# sx-HX711_V_1_0.net
KiCad netlist of a schematic drawn in EAGLE
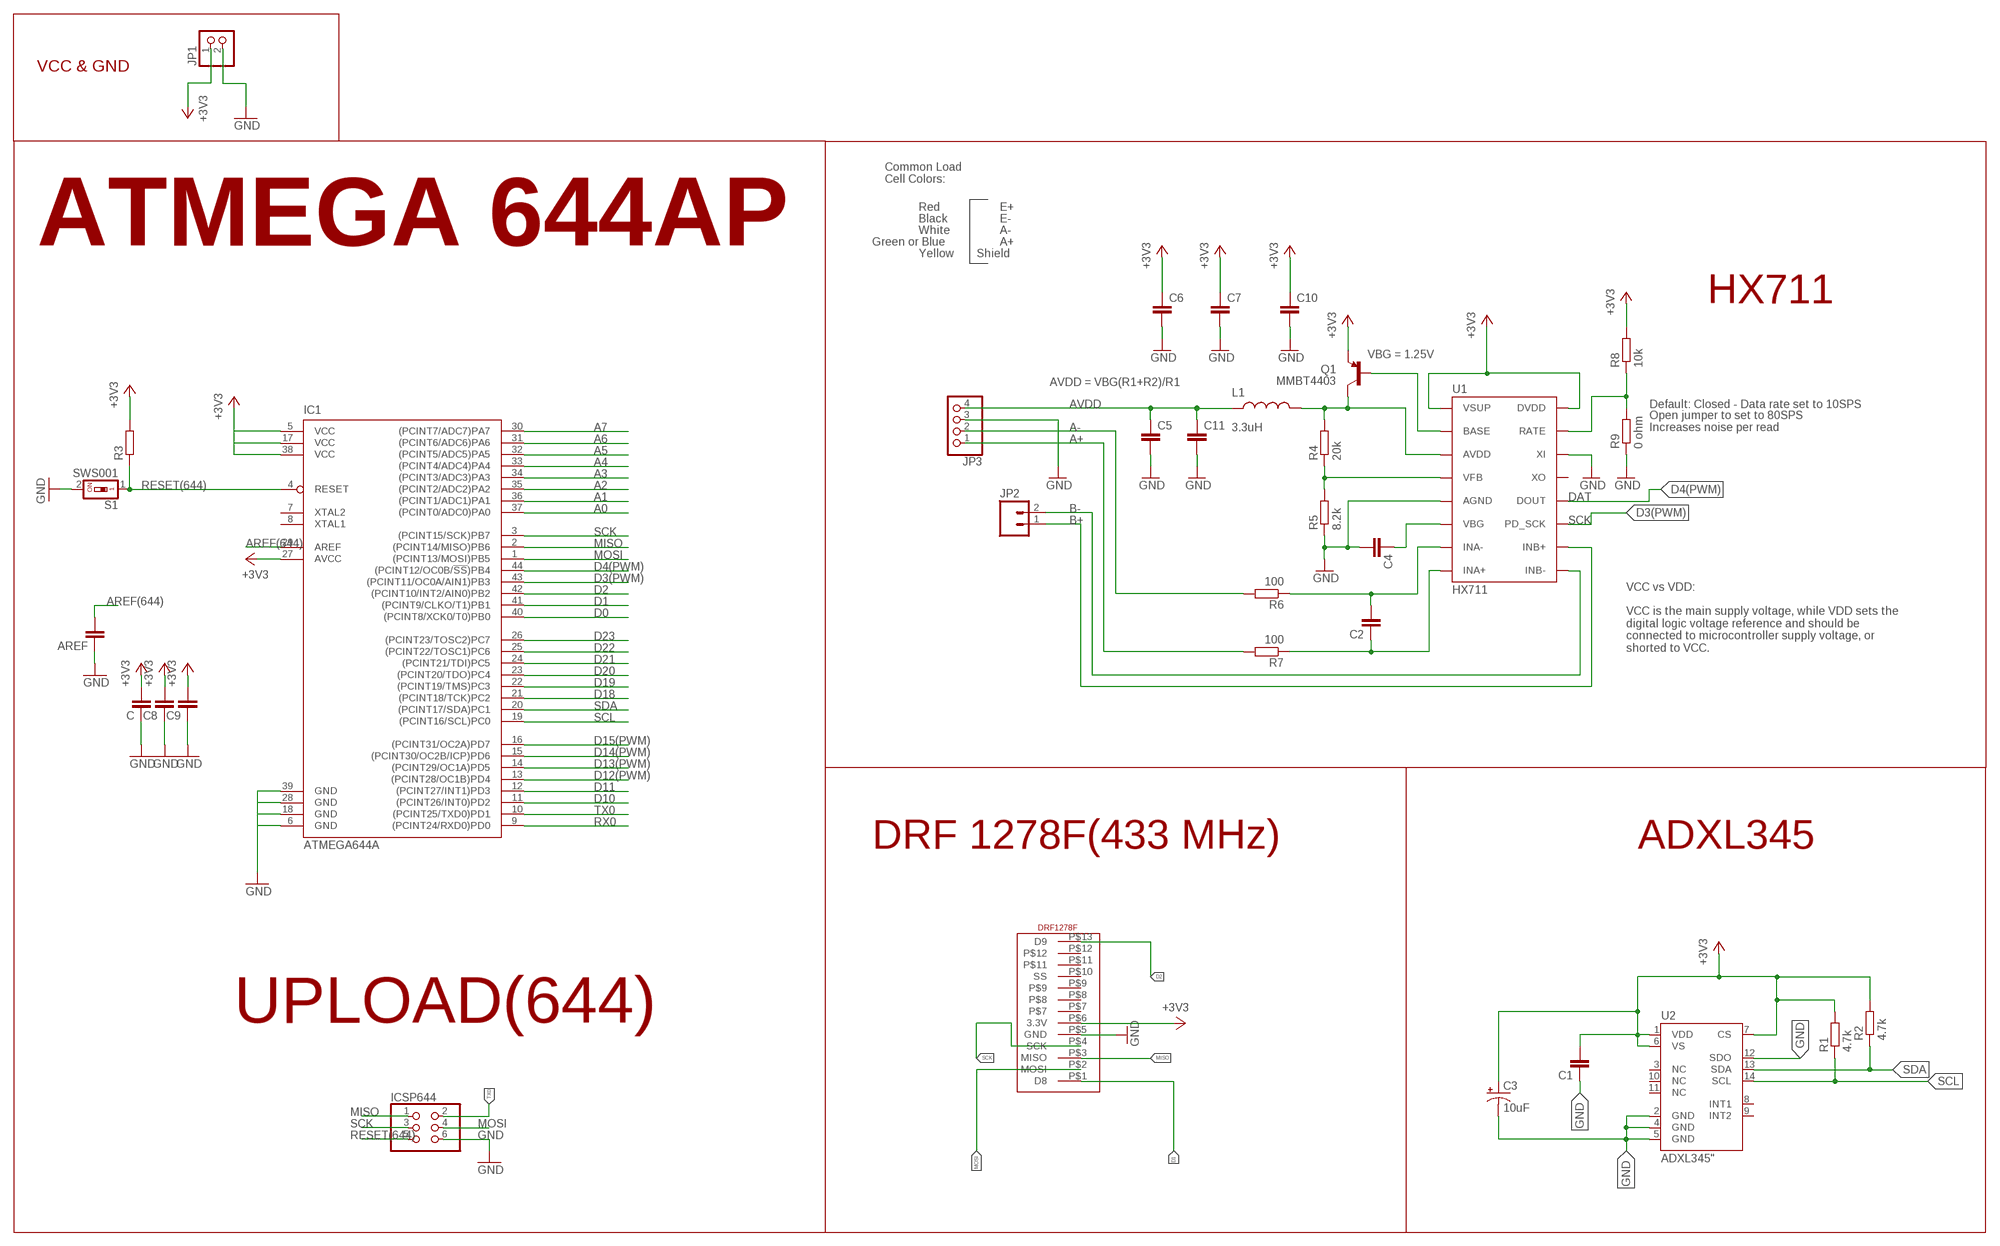
[diagram p0: schematic, sheet 1]

(export (version "E")
  (design (tool "Eeschema 10.0.6"))
  (components
    (comp (ref "AREF")
      (value "100nF")
      (footprint "eagle-import:C0805")
      (libsource (lib "eagle-import") (part "C-EUC0805"))
    )
    (comp (ref "C")
      (value "22 uF")
      (footprint "eagle-import:C0805")
      (libsource (lib "eagle-import") (part "C-EUC0805"))
    )
    (comp (ref "C1")
      (value "0.1uF")
      (footprint "eagle-import:C0805")
      (libsource (lib "eagle-import") (part "C-EUC0805"))
    )
    (comp (ref "C2")
      (value "0.1uF")
      (footprint "eagle-import:C0805")
      (libsource (lib "eagle-import") (part "C-EUC0805"))
    )
    (comp (ref "C3")
      (value "10uF")
      (footprint "eagle-import:EIA3216")
      (libsource (lib "eagle-import") (part "CAP_POL1206"))
    )
    (comp (ref "C4")
      (value "0.1uF")
      (footprint "eagle-import:C0805")
      (libsource (lib "eagle-import") (part "C-EUC0805"))
    )
    (comp (ref "C5")
      (value "0.1uF")
      (footprint "eagle-import:C0805")
      (libsource (lib "eagle-import") (part "C-EUC0805"))
    )
    (comp (ref "C6")
      (value "0.1uF")
      (footprint "eagle-import:C0805")
      (libsource (lib "eagle-import") (part "C-EUC0805"))
    )
    (comp (ref "C7")
      (value "0.1uF")
      (footprint "eagle-import:C0805")
      (libsource (lib "eagle-import") (part "C-EUC0805"))
    )
    (comp (ref "C8")
      (value "100nF")
      (footprint "eagle-import:C0805")
      (libsource (lib "eagle-import") (part "C-EUC0805"))
    )
    (comp (ref "C9")
      (value "100nF")
      (footprint "eagle-import:C0805")
      (libsource (lib "eagle-import") (part "C-EUC0805"))
    )
    (comp (ref "C10")
      (value "10uF")
      (footprint "eagle-import:C0805")
      (libsource (lib "eagle-import") (part "C-EUC0805"))
    )
    (comp (ref "C11")
      (value "10uF")
      (footprint "eagle-import:C0805")
      (libsource (lib "eagle-import") (part "C-EUC0805"))
    )
    (comp (ref "IC1")
      (value "ATMEGA644A")
      (footprint "eagle-import:TQFP44")
      (fields (field (name "MPN") "ATMEGA644PV-10AU"))
      (libsource (lib "eagle-import") (part "ATMEGA644A"))
    )
    (comp (ref "ICSP644")
      (value "PINHD-2X3")
      (footprint "eagle-import:2X03")
      (libsource (lib "eagle-import") (part "PINHD-2X3"))
    )
    (comp (ref "JP1")
      (value "PINHD-1X2")
      (footprint "eagle-import:1X02")
      (libsource (lib "eagle-import") (part "PINHD-1X2"))
    )
    (comp (ref "JP2")
      (value "M02PTH")
      (footprint "eagle-import:1X02")
      (libsource (lib "eagle-import") (part "M02PTH"))
    )
    (comp (ref "JP3")
      (value "PINHD-1X4")
      (footprint "eagle-import:1X04")
      (libsource (lib "eagle-import") (part "PINHD-1X4"))
    )
    (comp (ref "L1")
      (value "3.3uH")
      (footprint "eagle-import:0805")
      (libsource (lib "eagle-import") (part "INDUCTOR0805-IND"))
    )
    (comp (ref "Q1")
      (value "MMBT4403")
      (footprint "eagle-import:SOT23-3")
      (libsource (lib "eagle-import") (part "TRANSISTOR_PNPMMBT4403"))
    )
    (comp (ref "R1")
      (value "4.7k")
      (footprint "eagle-import:R0805")
      (libsource (lib "eagle-import") (part "R-EU_R0805"))
    )
    (comp (ref "R2")
      (value "4.7k")
      (footprint "eagle-import:R0805")
      (libsource (lib "eagle-import") (part "R-EU_R0805"))
    )
    (comp (ref "R3")
      (value "R-EU_R0805")
      (footprint "eagle-import:R0805")
      (libsource (lib "eagle-import") (part "R-EU_R0805"))
    )
    (comp (ref "R4")
      (value "20k")
      (footprint "eagle-import:R0805")
      (libsource (lib "eagle-import") (part "R-EU_R0805"))
    )
    (comp (ref "R5")
      (value "8.2k")
      (footprint "eagle-import:R0805")
      (libsource (lib "eagle-import") (part "R-EU_R0805"))
    )
    (comp (ref "R6")
      (value "100")
      (footprint "eagle-import:R0805")
      (libsource (lib "eagle-import") (part "R-EU_R0805"))
    )
    (comp (ref "R7")
      (value "100")
      (footprint "eagle-import:R0805")
      (libsource (lib "eagle-import") (part "R-EU_R0805"))
    )
    (comp (ref "R8")
      (value "10k")
      (footprint "eagle-import:R0805")
      (libsource (lib "eagle-import") (part "R-EU_R0805"))
    )
    (comp (ref "R9")
      (value "0 ohm")
      (footprint "eagle-import:R0805")
      (libsource (lib "eagle-import") (part "R-EU_R0805"))
    )
    (comp (ref "S1")
      (value "SWS001")
      (footprint "eagle-import:SMS-001")
      (libsource (lib "eagle-import") (part "SWS001"))
    )
    (comp (ref "U$1")
      (value "DRF1278F")
      (footprint "eagle-import:DIP13")
      (libsource (lib "eagle-import") (part "DRF1278F"))
    )
    (comp (ref "U1")
      (value "HX711")
      (footprint "eagle-import:SO16")
      (libsource (lib "eagle-import") (part "HX711HX711"))
    )
    (comp (ref "U2")
      (value "ADXL345\"")
      (footprint "eagle-import:ADXL3451_1")
      (libsource (lib "eagle-import") (part "ADXL345{dblquote}"))
    )
  )
  (nets
    (net (code "1") (name "+3V3") (class "Default")
      (node (ref "C") (pin "2") (pinfunction "2_2") (pintype "passive"))
      (node (ref "C1") (pin "2") (pinfunction "2_2") (pintype "passive"))
      (node (ref "C10") (pin "1") (pinfunction "1_1") (pintype "passive"))
      (node (ref "C3") (pin "A") (pinfunction "+_A") (pintype "passive"))
      (node (ref "C6") (pin "1") (pinfunction "1_1") (pintype "passive"))
      (node (ref "C7") (pin "1") (pinfunction "1_1") (pintype "passive"))
      (node (ref "C8") (pin "2") (pinfunction "2_2") (pintype "passive"))
      (node (ref "C9") (pin "2") (pinfunction "2_2") (pintype "passive"))
      (node (ref "IC1") (pin "17") (pinfunction "VCC_17") (pintype "power_in"))
      (node (ref "IC1") (pin "27") (pinfunction "AVCC_27") (pintype "power_in"))
      (node (ref "IC1") (pin "38") (pinfunction "VCC_38") (pintype "power_in"))
      (node (ref "IC1") (pin "5") (pinfunction "VCC_5") (pintype "power_in"))
      (node (ref "JP1") (pin "1") (pinfunction "1_1") (pintype "passive"))
      (node (ref "Q1") (pin "2") (pinfunction "E_2") (pintype "passive"))
      (node (ref "R1") (pin "2") (pinfunction "2_2") (pintype "passive"))
      (node (ref "R2") (pin "2") (pinfunction "2_2") (pintype "passive"))
      (node (ref "R3") (pin "2") (pinfunction "2_2") (pintype "passive"))
      (node (ref "R8") (pin "2") (pinfunction "2_2") (pintype "passive"))
      (node (ref "U$1") (pin "P$6") (pinfunction "3.3V_P$6") (pintype "bidirectional"))
      (node (ref "U1") (pin "1") (pinfunction "VSUP_1") (pintype "bidirectional"))
      (node (ref "U1") (pin "16") (pinfunction "DVDD_16") (pintype "bidirectional"))
      (node (ref "U2") (pin "1") (pinfunction "VDD_1") (pintype "bidirectional"))
      (node (ref "U2") (pin "6") (pinfunction "VS_6") (pintype "bidirectional"))
      (node (ref "U2") (pin "7") (pinfunction "CS_7") (pintype "bidirectional"))
    )
    (net (code "2") (name "/A+") (class "Default")
      (node (ref "JP3") (pin "1") (pinfunction "1_1") (pintype "passive"))
      (node (ref "R7") (pin "2") (pinfunction "2_2") (pintype "passive"))
    )
    (net (code "3") (name "/A-") (class "Default")
      (node (ref "JP3") (pin "2") (pinfunction "2_2") (pintype "passive"))
      (node (ref "R6") (pin "2") (pinfunction "2_2") (pintype "passive"))
    )
    (net (code "4") (name "/A0") (class "Default")
      (node (ref "IC1") (pin "37") (pinfunction "(PCINT0/ADC0)PA0_37") (pintype "bidirectional"))
    )
    (net (code "5") (name "/A1") (class "Default")
      (node (ref "IC1") (pin "36") (pinfunction "(PCINT1/ADC1)PA1_36") (pintype "bidirectional"))
    )
    (net (code "6") (name "/A2") (class "Default")
      (node (ref "IC1") (pin "35") (pinfunction "(PCINT2/ADC2)PA2_35") (pintype "bidirectional"))
    )
    (net (code "7") (name "/A3") (class "Default")
      (node (ref "IC1") (pin "34") (pinfunction "(PCINT3/ADC3)PA3_34") (pintype "bidirectional"))
    )
    (net (code "8") (name "/A4") (class "Default")
      (node (ref "IC1") (pin "33") (pinfunction "(PCINT4/ADC4)PA4_33") (pintype "bidirectional"))
    )
    (net (code "9") (name "/A5") (class "Default")
      (node (ref "IC1") (pin "32") (pinfunction "(PCINT5/ADC5)PA5_32") (pintype "bidirectional"))
    )
    (net (code "10") (name "/A6") (class "Default")
      (node (ref "IC1") (pin "31") (pinfunction "(PCINT6/ADC6)PA6_31") (pintype "bidirectional"))
    )
    (net (code "11") (name "/A7") (class "Default")
      (node (ref "IC1") (pin "30") (pinfunction "(PCINT7/ADC7)PA7_30") (pintype "bidirectional"))
    )
    (net (code "12") (name "/AREF(644)") (class "Default")
      (node (ref "AREF") (pin "2") (pinfunction "2_2") (pintype "passive"))
      (node (ref "IC1") (pin "29") (pinfunction "AREF_29") (pintype "passive"))
    )
    (net (code "13") (name "/AVDD") (class "Default")
      (node (ref "C11") (pin "1") (pinfunction "1_1") (pintype "passive"))
      (node (ref "C5") (pin "1") (pinfunction "1_1") (pintype "passive"))
      (node (ref "JP3") (pin "4") (pinfunction "4_4") (pintype "passive"))
      (node (ref "L1") (pin "1") (pinfunction "1_1") (pintype "passive"))
    )
    (net (code "14") (name "/B+") (class "Default")
      (node (ref "JP2") (pin "1") (pinfunction "1_1") (pintype "passive"))
      (node (ref "U1") (pin "10") (pinfunction "INB+_10") (pintype "bidirectional"))
    )
    (net (code "15") (name "/B-") (class "Default")
      (node (ref "JP2") (pin "2") (pinfunction "2_2") (pintype "passive"))
      (node (ref "U1") (pin "9") (pinfunction "INB-_9") (pintype "bidirectional"))
    )
    (net (code "16") (name "/D0") (class "Default")
      (node (ref "IC1") (pin "40") (pinfunction "(PCINT8/XCK0/T0)PB0_40") (pintype "bidirectional"))
    )
    (net (code "17") (name "/D10") (class "Default")
      (node (ref "IC1") (pin "11") (pinfunction "(PCINT26/INT0)PD2_11") (pintype "bidirectional"))
    )
    (net (code "18") (name "/D11") (class "Default")
      (node (ref "IC1") (pin "12") (pinfunction "(PCINT27/INT1)PD3_12") (pintype "bidirectional"))
    )
    (net (code "19") (name "/D12(PWM)") (class "Default")
      (node (ref "IC1") (pin "13") (pinfunction "(PCINT28/OC1B)PD4_13") (pintype "bidirectional"))
    )
    (net (code "20") (name "/D13(PWM)") (class "Default")
      (node (ref "IC1") (pin "14") (pinfunction "(PCINT29/OC1A)PD5_14") (pintype "bidirectional"))
    )
    (net (code "21") (name "/D14(PWM)") (class "Default")
      (node (ref "IC1") (pin "15") (pinfunction "(PCINT30/OC2B/ICP)PD6_15") (pintype "bidirectional"))
    )
    (net (code "22") (name "/D15(PWM)") (class "Default")
      (node (ref "IC1") (pin "16") (pinfunction "(PCINT31/OC2A)PD7_16") (pintype "bidirectional"))
    )
    (net (code "23") (name "/D18") (class "Default")
      (node (ref "IC1") (pin "21") (pinfunction "(PCINT18/TCK)PC2_21") (pintype "output"))
    )
    (net (code "24") (name "/D19") (class "Default")
      (node (ref "IC1") (pin "22") (pinfunction "(PCINT19/TMS)PC3_22") (pintype "output"))
    )
    (net (code "25") (name "/D20") (class "Default")
      (node (ref "IC1") (pin "23") (pinfunction "(PCINT20/TDO)PC4_23") (pintype "output"))
    )
    (net (code "26") (name "/D21") (class "Default")
      (node (ref "IC1") (pin "24") (pinfunction "(PCINT21/TDI)PC5_24") (pintype "output"))
    )
    (net (code "27") (name "/D22") (class "Default")
      (node (ref "IC1") (pin "25") (pinfunction "(PCINT22/TOSC1)PC6_25") (pintype "output"))
    )
    (net (code "28") (name "/D23") (class "Default")
      (node (ref "IC1") (pin "26") (pinfunction "(PCINT23/TOSC2)PC7_26") (pintype "output"))
    )
    (net (code "29") (name "/RESET(644)") (class "Default")
      (node (ref "IC1") (pin "4") (pinfunction "RESET_4") (pintype "input"))
      (node (ref "ICSP644") (pin "5") (pinfunction "5_5") (pintype "passive"))
      (node (ref "R3") (pin "1") (pinfunction "1_1") (pintype "passive"))
      (node (ref "S1") (pin "1") (pinfunction "1_1") (pintype "passive"))
    )
    (net (code "30") (name "/RX0") (class "Default")
      (node (ref "IC1") (pin "9") (pinfunction "(PCINT24/RXD0)PD0_9") (pintype "bidirectional"))
    )
    (net (code "31") (name "D1") (class "Default")
      (node (ref "IC1") (pin "41") (pinfunction "(PCINT9/CLKO/T1)PB1_41") (pintype "bidirectional"))
      (node (ref "U$1") (pin "P$1") (pinfunction "D8_P$1") (pintype "bidirectional"))
    )
    (net (code "32") (name "D2") (class "Default")
      (node (ref "IC1") (pin "42") (pinfunction "(PCINT10/INT2/AIN0)PB2_42") (pintype "bidirectional"))
      (node (ref "U$1") (pin "P$13") (pinfunction "D9_P$13") (pintype "bidirectional"))
    )
    (net (code "33") (name "D3(PWM)") (class "Default")
      (node (ref "IC1") (pin "43") (pinfunction "(PCINT11/OC0A/AIN1)PB3_43") (pintype "bidirectional"))
      (node (ref "U1") (pin "11") (pinfunction "PD_SCK_11") (pintype "bidirectional"))
    )
    (net (code "34") (name "D4(PWM)") (class "Default")
      (node (ref "IC1") (pin "44") (pinfunction "(PCINT12/OC0B/~{SS})PB4_44") (pintype "bidirectional"))
      (node (ref "U1") (pin "12") (pinfunction "DOUT_12") (pintype "bidirectional"))
    )
    (net (code "35") (name "GND") (class "Default")
      (node (ref "AREF") (pin "1") (pinfunction "1_1") (pintype "passive"))
      (node (ref "C") (pin "1") (pinfunction "1_1") (pintype "passive"))
      (node (ref "C1") (pin "1") (pinfunction "1_1") (pintype "passive"))
      (node (ref "C10") (pin "2") (pinfunction "2_2") (pintype "passive"))
      (node (ref "C11") (pin "2") (pinfunction "2_2") (pintype "passive"))
      (node (ref "C3") (pin "C") (pinfunction "-_C") (pintype "passive"))
      (node (ref "C4") (pin "2") (pinfunction "2_2") (pintype "passive"))
      (node (ref "C5") (pin "2") (pinfunction "2_2") (pintype "passive"))
      (node (ref "C6") (pin "2") (pinfunction "2_2") (pintype "passive"))
      (node (ref "C7") (pin "2") (pinfunction "2_2") (pintype "passive"))
      (node (ref "C8") (pin "1") (pinfunction "1_1") (pintype "passive"))
      (node (ref "C9") (pin "1") (pinfunction "1_1") (pintype "passive"))
      (node (ref "IC1") (pin "18") (pinfunction "GND_18") (pintype "power_in"))
      (node (ref "IC1") (pin "28") (pinfunction "GND_28") (pintype "power_in"))
      (node (ref "IC1") (pin "39") (pinfunction "GND_39") (pintype "power_in"))
      (node (ref "IC1") (pin "6") (pinfunction "GND_6") (pintype "power_in"))
      (node (ref "ICSP644") (pin "6") (pinfunction "6_6") (pintype "passive"))
      (node (ref "JP1") (pin "2") (pinfunction "2_2") (pintype "passive"))
      (node (ref "JP3") (pin "3") (pinfunction "3_3") (pintype "passive"))
      (node (ref "R5") (pin "1") (pinfunction "1_1") (pintype "passive"))
      (node (ref "R9") (pin "1") (pinfunction "1_1") (pintype "passive"))
      (node (ref "S1") (pin "2") (pinfunction "2_2") (pintype "passive"))
      (node (ref "U$1") (pin "P$5") (pinfunction "GND_P$5") (pintype "bidirectional"))
      (node (ref "U1") (pin "14") (pinfunction "XI_14") (pintype "bidirectional"))
      (node (ref "U1") (pin "5") (pinfunction "AGND_5") (pintype "bidirectional"))
      (node (ref "U2") (pin "12") (pinfunction "SDO_12") (pintype "bidirectional"))
      (node (ref "U2") (pin "2") (pinfunction "GND_2") (pintype "bidirectional"))
      (node (ref "U2") (pin "4") (pinfunction "GND_4") (pintype "bidirectional"))
      (node (ref "U2") (pin "5") (pinfunction "GND_5") (pintype "bidirectional"))
    )
    (net (code "36") (name "MISO") (class "Default")
      (node (ref "IC1") (pin "2") (pinfunction "(PCINT14/MISO)PB6_2") (pintype "bidirectional"))
      (node (ref "ICSP644") (pin "1") (pinfunction "1_1") (pintype "passive"))
      (node (ref "U$1") (pin "P$3") (pinfunction "MISO_P$3") (pintype "bidirectional"))
    )
    (net (code "37") (name "MOSI") (class "Default")
      (node (ref "IC1") (pin "1") (pinfunction "(PCINT13/MOSI)PB5_1") (pintype "bidirectional"))
      (node (ref "ICSP644") (pin "4") (pinfunction "4_4") (pintype "passive"))
      (node (ref "U$1") (pin "P$2") (pinfunction "MOSI_P$2") (pintype "bidirectional"))
    )
    (net (code "38") (name "Net-(Q1-B)") (class "Default")
      (node (ref "Q1") (pin "1") (pinfunction "B_1") (pintype "passive"))
      (node (ref "U1") (pin "2") (pinfunction "BASE_2") (pintype "bidirectional"))
    )
    (net (code "39") (name "Net-(Q1-C)") (class "Default")
      (node (ref "L1") (pin "2") (pinfunction "2_2") (pintype "passive"))
      (node (ref "Q1") (pin "3") (pinfunction "C_3") (pintype "passive"))
      (node (ref "R4") (pin "2") (pinfunction "2_2") (pintype "passive"))
      (node (ref "U1") (pin "3") (pinfunction "AVDD_3") (pintype "bidirectional"))
    )
    (net (code "40") (name "Net-(U1-INA+)") (class "Default")
      (node (ref "C2") (pin "1") (pinfunction "1_1") (pintype "passive"))
      (node (ref "R7") (pin "1") (pinfunction "1_1") (pintype "passive"))
      (node (ref "U1") (pin "8") (pinfunction "INA+_8") (pintype "bidirectional"))
    )
    (net (code "41") (name "Net-(U1-INA-)") (class "Default")
      (node (ref "C2") (pin "2") (pinfunction "2_2") (pintype "passive"))
      (node (ref "R6") (pin "1") (pinfunction "1_1") (pintype "passive"))
      (node (ref "U1") (pin "7") (pinfunction "INA-_7") (pintype "bidirectional"))
    )
    (net (code "42") (name "Net-(U1-RATE)") (class "Default")
      (node (ref "R8") (pin "1") (pinfunction "1_1") (pintype "passive"))
      (node (ref "R9") (pin "2") (pinfunction "2_2") (pintype "passive"))
      (node (ref "U1") (pin "15") (pinfunction "RATE_15") (pintype "bidirectional"))
    )
    (net (code "43") (name "Net-(U1-VBG)") (class "Default")
      (node (ref "C4") (pin "1") (pinfunction "1_1") (pintype "passive"))
      (node (ref "U1") (pin "6") (pinfunction "VBG_6") (pintype "bidirectional"))
    )
    (net (code "44") (name "Net-(U1-VFB)") (class "Default")
      (node (ref "R4") (pin "1") (pinfunction "1_1") (pintype "passive"))
      (node (ref "R5") (pin "2") (pinfunction "2_2") (pintype "passive"))
      (node (ref "U1") (pin "4") (pinfunction "VFB_4") (pintype "bidirectional"))
    )
    (net (code "45") (name "SCK") (class "Default")
      (node (ref "IC1") (pin "3") (pinfunction "(PCINT15/SCK)PB7_3") (pintype "bidirectional"))
      (node (ref "ICSP644") (pin "3") (pinfunction "3_3") (pintype "passive"))
      (node (ref "U$1") (pin "P$4") (pinfunction "SCK_P$4") (pintype "bidirectional"))
    )
    (net (code "46") (name "SCL") (class "Default")
      (node (ref "IC1") (pin "19") (pinfunction "(PCINT16/SCL)PC0_19") (pintype "output"))
      (node (ref "R1") (pin "1") (pinfunction "1_1") (pintype "passive"))
      (node (ref "U2") (pin "14") (pinfunction "SCL_14") (pintype "bidirectional"))
    )
    (net (code "47") (name "SDA") (class "Default")
      (node (ref "IC1") (pin "20") (pinfunction "(PCINT17/SDA)PC1_20") (pintype "output"))
      (node (ref "R2") (pin "1") (pinfunction "1_1") (pintype "passive"))
      (node (ref "U2") (pin "13") (pinfunction "SDA_13") (pintype "bidirectional"))
    )
    (net (code "48") (name "TX0") (class "Default")
      (node (ref "IC1") (pin "10") (pinfunction "(PCINT25/TXD0)PD1_10") (pintype "bidirectional"))
      (node (ref "ICSP644") (pin "2") (pinfunction "2_2") (pintype "passive"))
    )
    (net (code "49") (name "unconnected-(IC1-XTAL1-Pad8)") (class "Default")
      (node (ref "IC1") (pin "8") (pinfunction "XTAL1_8") (pintype "bidirectional"))
    )
    (net (code "50") (name "unconnected-(IC1-XTAL2-Pad7)") (class "Default")
      (node (ref "IC1") (pin "7") (pinfunction "XTAL2_7") (pintype "bidirectional"))
    )
    (net (code "51") (name "unconnected-(U$1-PadP$7)") (class "Default")
      (node (ref "U$1") (pin "P$7") (pinfunction "P$7_P$7") (pintype "bidirectional"))
    )
    (net (code "52") (name "unconnected-(U$1-PadP$8)") (class "Default")
      (node (ref "U$1") (pin "P$8") (pinfunction "P$8_P$8") (pintype "bidirectional"))
    )
    (net (code "53") (name "unconnected-(U$1-PadP$9)") (class "Default")
      (node (ref "U$1") (pin "P$9") (pinfunction "P$9_P$9") (pintype "bidirectional"))
    )
    (net (code "54") (name "unconnected-(U$1-PadP$11)") (class "Default")
      (node (ref "U$1") (pin "P$11") (pinfunction "P$11_P$11") (pintype "bidirectional"))
    )
    (net (code "55") (name "unconnected-(U$1-PadP$12)") (class "Default")
      (node (ref "U$1") (pin "P$12") (pinfunction "P$12_P$12") (pintype "bidirectional"))
    )
    (net (code "56") (name "unconnected-(U$1-SS-PadP$10)") (class "Default")
      (node (ref "U$1") (pin "P$10") (pinfunction "SS_P$10") (pintype "bidirectional"))
    )
    (net (code "57") (name "unconnected-(U1-XO-Pad13)") (class "Default")
      (node (ref "U1") (pin "13") (pinfunction "XO_13") (pintype "bidirectional"))
    )
    (net (code "58") (name "unconnected-(U2-INT1-Pad8)") (class "Default")
      (node (ref "U2") (pin "8") (pinfunction "INT1_8") (pintype "bidirectional"))
    )
    (net (code "59") (name "unconnected-(U2-INT2-Pad9)") (class "Default")
      (node (ref "U2") (pin "9") (pinfunction "INT2_9") (pintype "bidirectional"))
    )
    (net (code "60") (name "unconnected-(U2-NC-Pad3)") (class "Default")
      (node (ref "U2") (pin "3") (pinfunction "NC_3") (pintype "bidirectional"))
    )
    (net (code "61") (name "unconnected-(U2-NC-Pad10)") (class "Default")
      (node (ref "U2") (pin "10") (pinfunction "NC_10") (pintype "bidirectional"))
    )
    (net (code "62") (name "unconnected-(U2-NC-Pad11)") (class "Default")
      (node (ref "U2") (pin "11") (pinfunction "NC_11") (pintype "bidirectional"))
    )
  )
)
